# CONNECTEUR_3.net
KiCad netlist of a schematic drawn in Altium Designer
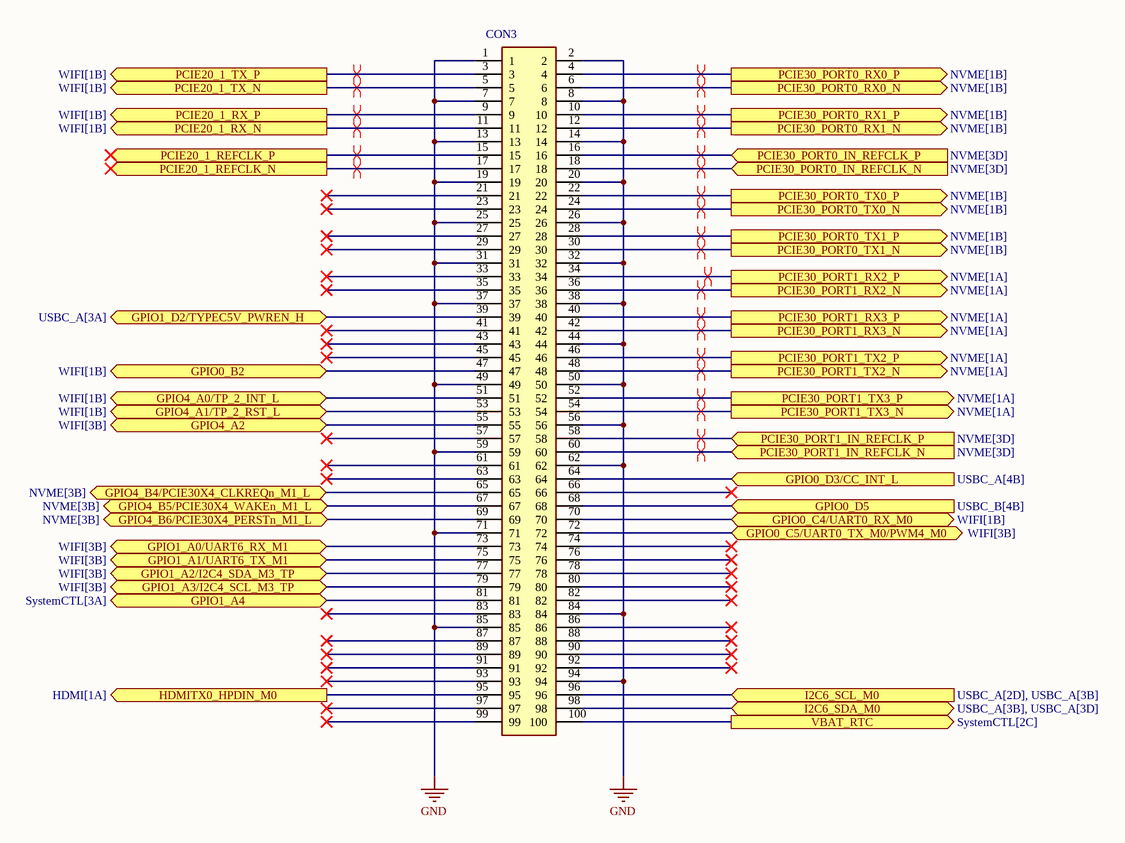
[diagram p0: CONNECTEUR_3.SchDoc]

(export (version "E")
  (design (tool "Eeschema 10.0.6"))
  (components
    (comp (ref "CON3")
      (value "DF40HC")
      (footprint "DF40HC30100DS04V51_MOD")
      (description "Stacking Board Connector, DF40 Series, Receptacle, 0.4 mm, 100, Surface Mount, G")
      (fields
        (field (name "MANUFACTURER_PART_NUMBER") "DF40HC(3.0)-100DS-0.4V(51")
        (field (name "MOUSER PART NUMBER") "798-DF40HC30100DS451")
      )
      (libsource (lib "DARKYDEN") (part "DF40HC(3.0)-100DS-0.4V(51)"))
    )
  )
  (nets
    (net (code "1") (name "/GPIO0_B2") (class "Default")
      (node (ref "CON3") (pin "47") (pinfunction "47_47") (pintype "passive"))
    )
    (net (code "2") (name "/GPIO0_C4{slash}UART0_RX_M0") (class "Default")
      (node (ref "CON3") (pin "70") (pinfunction "70_70") (pintype "passive"))
    )
    (net (code "3") (name "/GPIO0_C5{slash}UART0_TX_M0{slash}PWM4_M0") (class "Default")
      (node (ref "CON3") (pin "72") (pinfunction "72_72") (pintype "passive"))
    )
    (net (code "4") (name "/GPIO0_D3{slash}CC_INT_L") (class "Default")
      (node (ref "CON3") (pin "64") (pinfunction "64_64") (pintype "passive"))
    )
    (net (code "5") (name "/GPIO0_D5") (class "Default")
      (node (ref "CON3") (pin "68") (pinfunction "68_68") (pintype "passive"))
    )
    (net (code "6") (name "/GPIO1_A0{slash}UART6_RX_M1") (class "Default")
      (node (ref "CON3") (pin "73") (pinfunction "73_73") (pintype "passive"))
    )
    (net (code "7") (name "/GPIO1_A1{slash}UART6_TX_M1") (class "Default")
      (node (ref "CON3") (pin "75") (pinfunction "75_75") (pintype "passive"))
    )
    (net (code "8") (name "/GPIO1_A2{slash}I2C4_SDA_M3_TP") (class "Default")
      (node (ref "CON3") (pin "77") (pinfunction "77_77") (pintype "passive"))
    )
    (net (code "9") (name "/GPIO1_A3{slash}I2C4_SCL_M3_TP") (class "Default")
      (node (ref "CON3") (pin "79") (pinfunction "79_79") (pintype "passive"))
    )
    (net (code "10") (name "/GPIO1_A4") (class "Default")
      (node (ref "CON3") (pin "81") (pinfunction "81_81") (pintype "passive"))
    )
    (net (code "11") (name "/GPIO1_D2{slash}TYPEC5V_PWREN_H") (class "Default")
      (node (ref "CON3") (pin "39") (pinfunction "39_39") (pintype "passive"))
    )
    (net (code "12") (name "/GPIO4_A0{slash}TP_2_INT_L") (class "Default")
      (node (ref "CON3") (pin "51") (pinfunction "51_51") (pintype "passive"))
    )
    (net (code "13") (name "/GPIO4_A1{slash}TP_2_RST_L") (class "Default")
      (node (ref "CON3") (pin "53") (pinfunction "53_53") (pintype "passive"))
    )
    (net (code "14") (name "/GPIO4_A2") (class "Default")
      (node (ref "CON3") (pin "55") (pinfunction "55_55") (pintype "passive"))
    )
    (net (code "15") (name "/GPIO4_B4{slash}PCIE30X4_CLKREQn_M1_L") (class "Default")
      (node (ref "CON3") (pin "65") (pinfunction "65_65") (pintype "passive"))
    )
    (net (code "16") (name "/GPIO4_B5{slash}PCIE30X4_WAKEn_M1_L") (class "Default")
      (node (ref "CON3") (pin "67") (pinfunction "67_67") (pintype "passive"))
    )
    (net (code "17") (name "/GPIO4_B6{slash}PCIE30X4_PERSTn_M1_L") (class "Default")
      (node (ref "CON3") (pin "69") (pinfunction "69_69") (pintype "passive"))
    )
    (net (code "18") (name "/HDMITX0_HPDIN_M0") (class "Default")
      (node (ref "CON3") (pin "95") (pinfunction "95_95") (pintype "passive"))
    )
    (net (code "19") (name "/I2C6_SCL_M0") (class "Default")
      (node (ref "CON3") (pin "96") (pinfunction "96_96") (pintype "passive"))
    )
    (net (code "20") (name "/I2C6_SDA_M0") (class "Default")
      (node (ref "CON3") (pin "98") (pinfunction "98_98") (pintype "passive"))
    )
    (net (code "21") (name "/PCIE20_1_REFCLK_N") (class "Default")
      (node (ref "CON3") (pin "17") (pinfunction "17_17") (pintype "passive"))
    )
    (net (code "22") (name "/PCIE20_1_REFCLK_P") (class "Default")
      (node (ref "CON3") (pin "15") (pinfunction "15_15") (pintype "passive"))
    )
    (net (code "23") (name "/PCIE20_1_RX_N") (class "Default")
      (node (ref "CON3") (pin "11") (pinfunction "11_11") (pintype "passive"))
    )
    (net (code "24") (name "/PCIE20_1_RX_P") (class "Default")
      (node (ref "CON3") (pin "9") (pinfunction "9_9") (pintype "passive"))
    )
    (net (code "25") (name "/PCIE20_1_TX_N") (class "Default")
      (node (ref "CON3") (pin "5") (pinfunction "5_5") (pintype "passive"))
    )
    (net (code "26") (name "/PCIE20_1_TX_P") (class "Default")
      (node (ref "CON3") (pin "3") (pinfunction "3_3") (pintype "passive"))
    )
    (net (code "27") (name "/PCIE30_PORT0_IN_REFCLK_N") (class "Default")
      (node (ref "CON3") (pin "18") (pinfunction "18_18") (pintype "passive"))
    )
    (net (code "28") (name "/PCIE30_PORT0_IN_REFCLK_P") (class "Default")
      (node (ref "CON3") (pin "16") (pinfunction "16_16") (pintype "passive"))
    )
    (net (code "29") (name "/PCIE30_PORT0_RX0_N") (class "Default")
      (node (ref "CON3") (pin "6") (pinfunction "6_6") (pintype "passive"))
    )
    (net (code "30") (name "/PCIE30_PORT0_RX0_P") (class "Default")
      (node (ref "CON3") (pin "4") (pinfunction "4_4") (pintype "passive"))
    )
    (net (code "31") (name "/PCIE30_PORT0_RX1_N") (class "Default")
      (node (ref "CON3") (pin "12") (pinfunction "12_12") (pintype "passive"))
    )
    (net (code "32") (name "/PCIE30_PORT0_RX1_P") (class "Default")
      (node (ref "CON3") (pin "10") (pinfunction "10_10") (pintype "passive"))
    )
    (net (code "33") (name "/PCIE30_PORT0_TX0_N") (class "Default")
      (node (ref "CON3") (pin "24") (pinfunction "24_24") (pintype "passive"))
    )
    (net (code "34") (name "/PCIE30_PORT0_TX0_P") (class "Default")
      (node (ref "CON3") (pin "22") (pinfunction "22_22") (pintype "passive"))
    )
    (net (code "35") (name "/PCIE30_PORT0_TX1_N") (class "Default")
      (node (ref "CON3") (pin "30") (pinfunction "30_30") (pintype "passive"))
    )
    (net (code "36") (name "/PCIE30_PORT0_TX1_P") (class "Default")
      (node (ref "CON3") (pin "28") (pinfunction "28_28") (pintype "passive"))
    )
    (net (code "37") (name "/PCIE30_PORT1_IN_REFCLK_N") (class "Default")
      (node (ref "CON3") (pin "60") (pinfunction "60_60") (pintype "passive"))
    )
    (net (code "38") (name "/PCIE30_PORT1_IN_REFCLK_P") (class "Default")
      (node (ref "CON3") (pin "58") (pinfunction "58_58") (pintype "passive"))
    )
    (net (code "39") (name "/PCIE30_PORT1_RX2_N") (class "Default")
      (node (ref "CON3") (pin "36") (pinfunction "36_36") (pintype "passive"))
    )
    (net (code "40") (name "/PCIE30_PORT1_RX2_P") (class "Default")
      (node (ref "CON3") (pin "34") (pinfunction "34_34") (pintype "passive"))
    )
    (net (code "41") (name "/PCIE30_PORT1_RX3_N") (class "Default")
      (node (ref "CON3") (pin "42") (pinfunction "42_42") (pintype "passive"))
    )
    (net (code "42") (name "/PCIE30_PORT1_RX3_P") (class "Default")
      (node (ref "CON3") (pin "40") (pinfunction "40_40") (pintype "passive"))
    )
    (net (code "43") (name "/PCIE30_PORT1_TX2_N") (class "Default")
      (node (ref "CON3") (pin "48") (pinfunction "48_48") (pintype "passive"))
    )
    (net (code "44") (name "/PCIE30_PORT1_TX2_P") (class "Default")
      (node (ref "CON3") (pin "46") (pinfunction "46_46") (pintype "passive"))
    )
    (net (code "45") (name "/PCIE30_PORT1_TX3_N") (class "Default")
      (node (ref "CON3") (pin "54") (pinfunction "54_54") (pintype "passive"))
    )
    (net (code "46") (name "/PCIE30_PORT1_TX3_P") (class "Default")
      (node (ref "CON3") (pin "52") (pinfunction "52_52") (pintype "passive"))
    )
    (net (code "47") (name "/VBAT_RTC") (class "Default")
      (node (ref "CON3") (pin "100") (pinfunction "100_100") (pintype "passive"))
    )
    (net (code "48") (name "GND") (class "Default")
      (node (ref "CON3") (pin "1") (pinfunction "1_1") (pintype "passive"))
      (node (ref "CON3") (pin "13") (pinfunction "13_13") (pintype "passive"))
      (node (ref "CON3") (pin "14") (pinfunction "14_14") (pintype "passive"))
      (node (ref "CON3") (pin "19") (pinfunction "19_19") (pintype "passive"))
      (node (ref "CON3") (pin "2") (pinfunction "2_2") (pintype "passive"))
      (node (ref "CON3") (pin "20") (pinfunction "20_20") (pintype "passive"))
      (node (ref "CON3") (pin "25") (pinfunction "25_25") (pintype "passive"))
      (node (ref "CON3") (pin "26") (pinfunction "26_26") (pintype "passive"))
      (node (ref "CON3") (pin "31") (pinfunction "31_31") (pintype "passive"))
      (node (ref "CON3") (pin "32") (pinfunction "32_32") (pintype "passive"))
      (node (ref "CON3") (pin "37") (pinfunction "37_37") (pintype "passive"))
      (node (ref "CON3") (pin "38") (pinfunction "38_38") (pintype "passive"))
      (node (ref "CON3") (pin "44") (pinfunction "44_44") (pintype "passive"))
      (node (ref "CON3") (pin "49") (pinfunction "49_49") (pintype "passive"))
      (node (ref "CON3") (pin "50") (pinfunction "50_50") (pintype "passive"))
      (node (ref "CON3") (pin "56") (pinfunction "56_56") (pintype "passive"))
      (node (ref "CON3") (pin "59") (pinfunction "59_59") (pintype "passive"))
      (node (ref "CON3") (pin "62") (pinfunction "62_62") (pintype "passive"))
      (node (ref "CON3") (pin "7") (pinfunction "7_7") (pintype "passive"))
      (node (ref "CON3") (pin "71") (pinfunction "71_71") (pintype "passive"))
      (node (ref "CON3") (pin "8") (pinfunction "8_8") (pintype "passive"))
      (node (ref "CON3") (pin "84") (pinfunction "84_84") (pintype "passive"))
      (node (ref "CON3") (pin "85") (pinfunction "85_85") (pintype "passive"))
      (node (ref "CON3") (pin "94") (pinfunction "94_94") (pintype "passive"))
    )
    (net (code "49") (name "unconnected-(CON3-Pad21)") (class "Default")
      (node (ref "CON3") (pin "21") (pinfunction "21_21") (pintype "passive+no_connect"))
    )
    (net (code "50") (name "unconnected-(CON3-Pad23)") (class "Default")
      (node (ref "CON3") (pin "23") (pinfunction "23_23") (pintype "passive+no_connect"))
    )
    (net (code "51") (name "unconnected-(CON3-Pad27)") (class "Default")
      (node (ref "CON3") (pin "27") (pinfunction "27_27") (pintype "passive+no_connect"))
    )
    (net (code "52") (name "unconnected-(CON3-Pad29)") (class "Default")
      (node (ref "CON3") (pin "29") (pinfunction "29_29") (pintype "passive+no_connect"))
    )
    (net (code "53") (name "unconnected-(CON3-Pad33)") (class "Default")
      (node (ref "CON3") (pin "33") (pinfunction "33_33") (pintype "passive+no_connect"))
    )
    (net (code "54") (name "unconnected-(CON3-Pad35)") (class "Default")
      (node (ref "CON3") (pin "35") (pinfunction "35_35") (pintype "passive+no_connect"))
    )
    (net (code "55") (name "unconnected-(CON3-Pad41)") (class "Default")
      (node (ref "CON3") (pin "41") (pinfunction "41_41") (pintype "passive+no_connect"))
    )
    (net (code "56") (name "unconnected-(CON3-Pad43)") (class "Default")
      (node (ref "CON3") (pin "43") (pinfunction "43_43") (pintype "passive+no_connect"))
    )
    (net (code "57") (name "unconnected-(CON3-Pad45)") (class "Default")
      (node (ref "CON3") (pin "45") (pinfunction "45_45") (pintype "passive+no_connect"))
    )
    (net (code "58") (name "unconnected-(CON3-Pad57)") (class "Default")
      (node (ref "CON3") (pin "57") (pinfunction "57_57") (pintype "passive+no_connect"))
    )
    (net (code "59") (name "unconnected-(CON3-Pad61)") (class "Default")
      (node (ref "CON3") (pin "61") (pinfunction "61_61") (pintype "passive+no_connect"))
    )
    (net (code "60") (name "unconnected-(CON3-Pad63)") (class "Default")
      (node (ref "CON3") (pin "63") (pinfunction "63_63") (pintype "passive+no_connect"))
    )
    (net (code "61") (name "unconnected-(CON3-Pad66)") (class "Default")
      (node (ref "CON3") (pin "66") (pinfunction "66_66") (pintype "passive+no_connect"))
    )
    (net (code "62") (name "unconnected-(CON3-Pad74)") (class "Default")
      (node (ref "CON3") (pin "74") (pinfunction "74_74") (pintype "passive+no_connect"))
    )
    (net (code "63") (name "unconnected-(CON3-Pad76)") (class "Default")
      (node (ref "CON3") (pin "76") (pinfunction "76_76") (pintype "passive+no_connect"))
    )
    (net (code "64") (name "unconnected-(CON3-Pad78)") (class "Default")
      (node (ref "CON3") (pin "78") (pinfunction "78_78") (pintype "passive+no_connect"))
    )
    (net (code "65") (name "unconnected-(CON3-Pad80)") (class "Default")
      (node (ref "CON3") (pin "80") (pinfunction "80_80") (pintype "passive+no_connect"))
    )
    (net (code "66") (name "unconnected-(CON3-Pad82)") (class "Default")
      (node (ref "CON3") (pin "82") (pinfunction "82_82") (pintype "passive+no_connect"))
    )
    (net (code "67") (name "unconnected-(CON3-Pad83)") (class "Default")
      (node (ref "CON3") (pin "83") (pinfunction "83_83") (pintype "passive+no_connect"))
    )
    (net (code "68") (name "unconnected-(CON3-Pad86)") (class "Default")
      (node (ref "CON3") (pin "86") (pinfunction "86_86") (pintype "passive+no_connect"))
    )
    (net (code "69") (name "unconnected-(CON3-Pad87)") (class "Default")
      (node (ref "CON3") (pin "87") (pinfunction "87_87") (pintype "passive+no_connect"))
    )
    (net (code "70") (name "unconnected-(CON3-Pad88)") (class "Default")
      (node (ref "CON3") (pin "88") (pinfunction "88_88") (pintype "passive+no_connect"))
    )
    (net (code "71") (name "unconnected-(CON3-Pad89)") (class "Default")
      (node (ref "CON3") (pin "89") (pinfunction "89_89") (pintype "passive+no_connect"))
    )
    (net (code "72") (name "unconnected-(CON3-Pad90)") (class "Default")
      (node (ref "CON3") (pin "90") (pinfunction "90_90") (pintype "passive+no_connect"))
    )
    (net (code "73") (name "unconnected-(CON3-Pad91)") (class "Default")
      (node (ref "CON3") (pin "91") (pinfunction "91_91") (pintype "passive+no_connect"))
    )
    (net (code "74") (name "unconnected-(CON3-Pad92)") (class "Default")
      (node (ref "CON3") (pin "92") (pinfunction "92_92") (pintype "passive+no_connect"))
    )
    (net (code "75") (name "unconnected-(CON3-Pad93)") (class "Default")
      (node (ref "CON3") (pin "93") (pinfunction "93_93") (pintype "passive+no_connect"))
    )
    (net (code "76") (name "unconnected-(CON3-Pad97)") (class "Default")
      (node (ref "CON3") (pin "97") (pinfunction "97_97") (pintype "passive+no_connect"))
    )
    (net (code "77") (name "unconnected-(CON3-Pad99)") (class "Default")
      (node (ref "CON3") (pin "99") (pinfunction "99_99") (pintype "passive+no_connect"))
    )
  )
)
